# main.net
KiCad netlist of a schematic drawn in Altium Designer
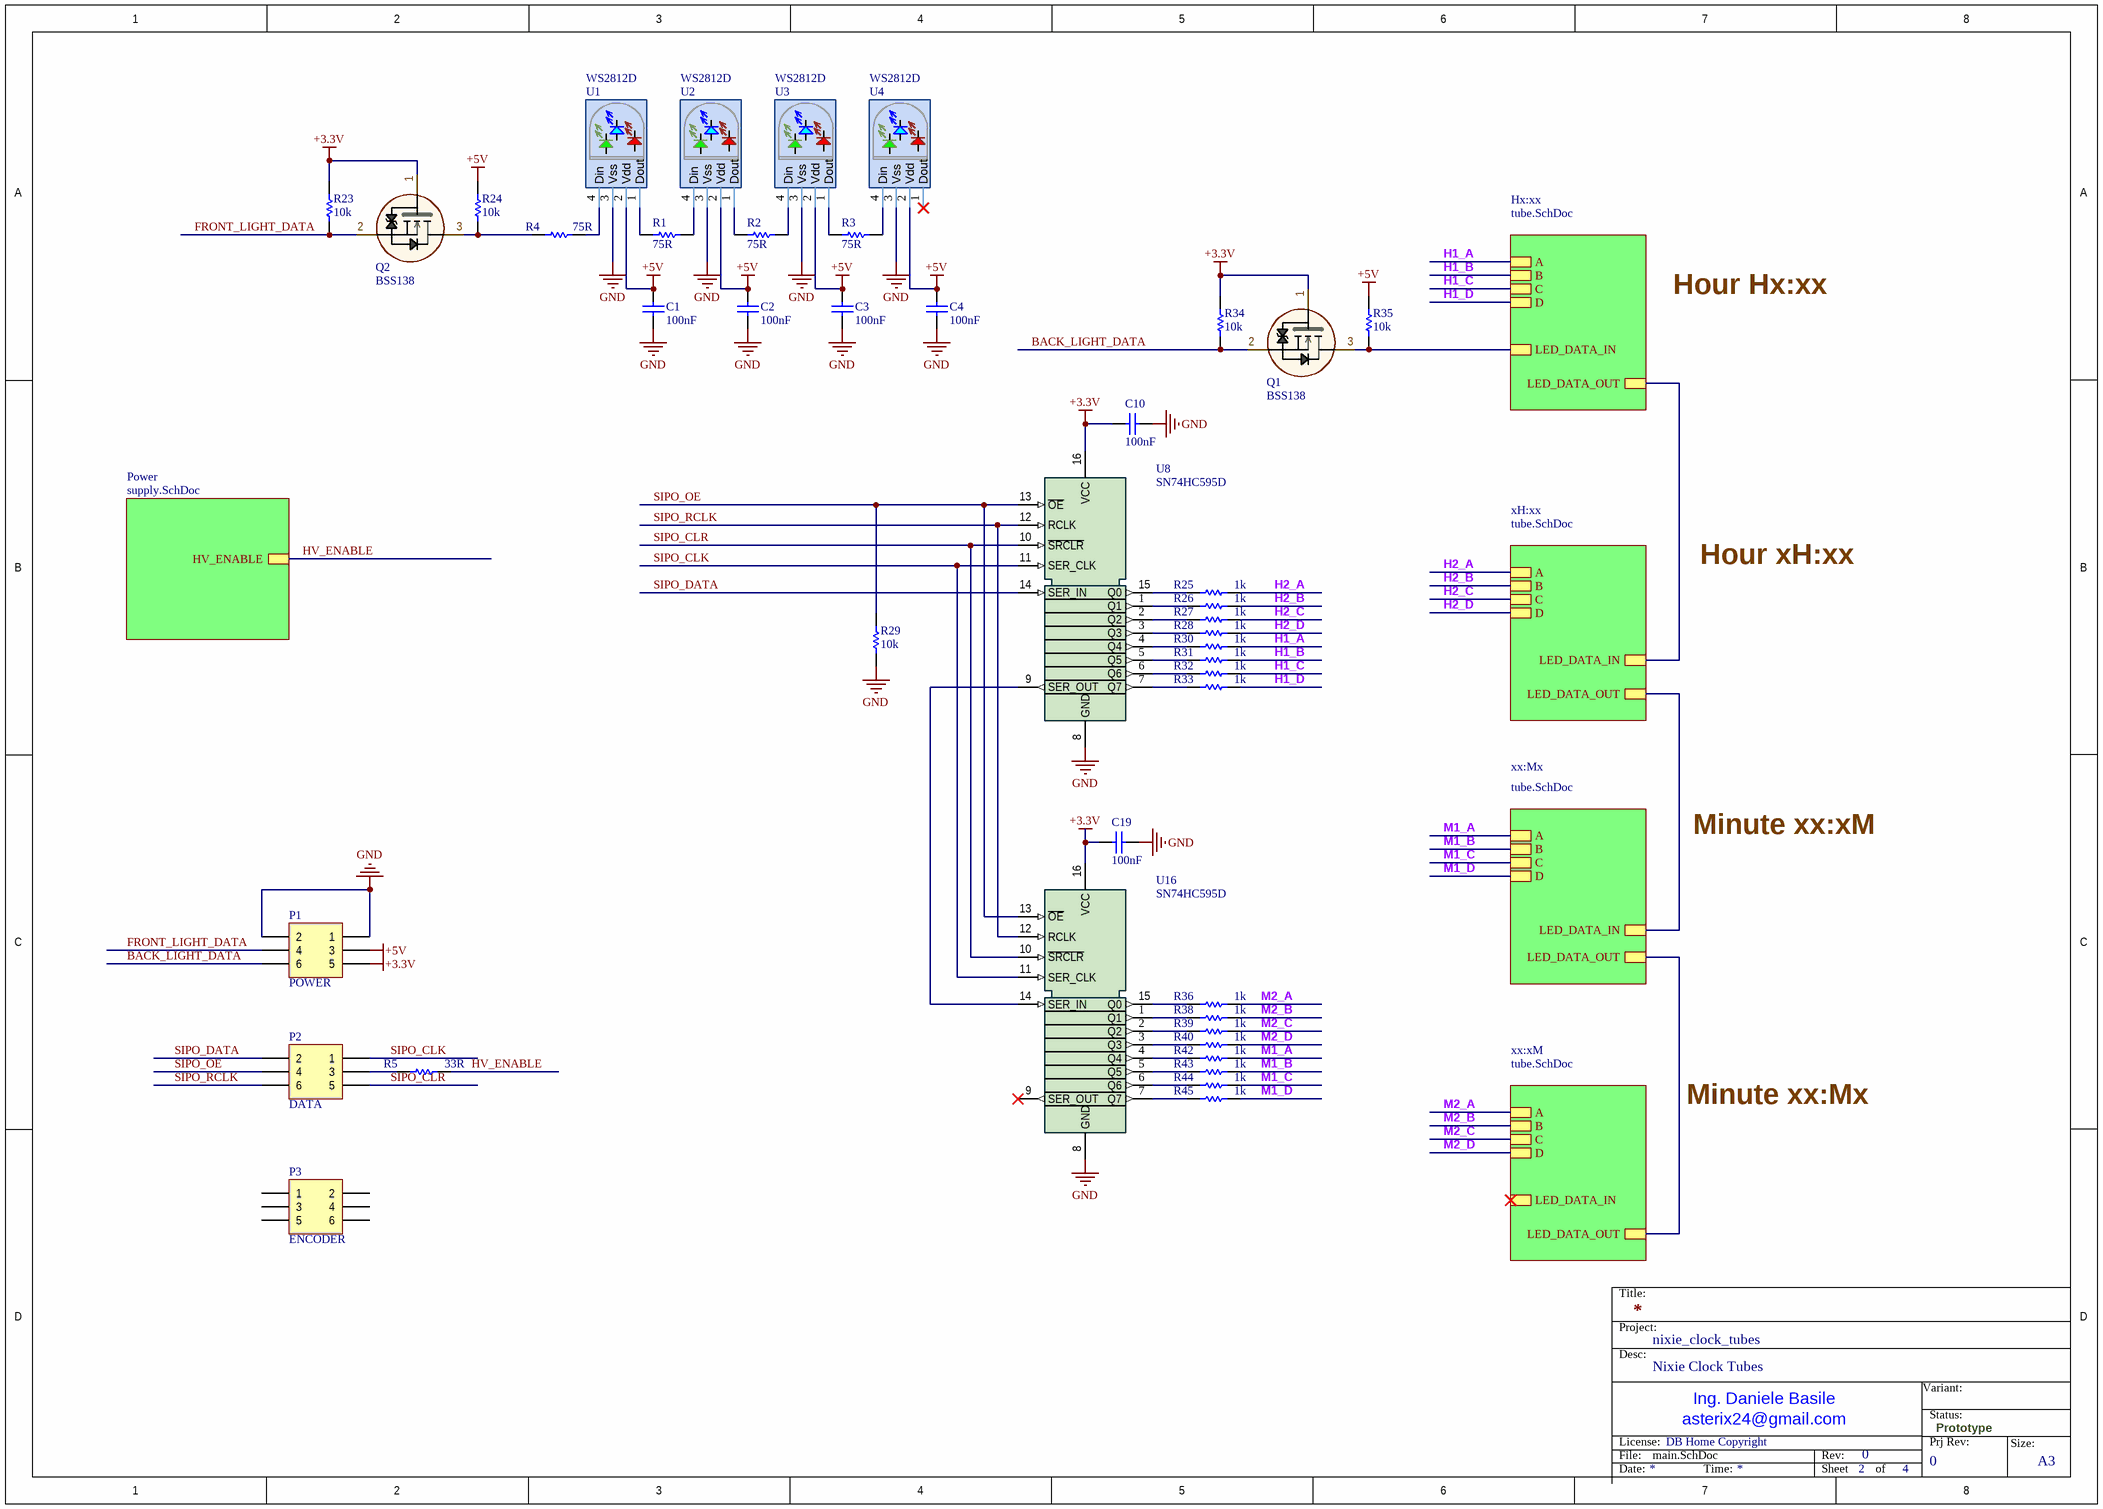
[diagram p0: main.SchDoc]

(export (version "E")
  (design (tool "Eeschema 10.0.6"))
  (components
    (comp (ref "C1")
      (value "100nF")
      (footprint "0603_[1608]")
      (description "Capacitor")
      (libsource (lib "develer_generic") (part "Cap"))
    )
    (comp (ref "C2")
      (value "100nF")
      (footprint "0603_[1608]")
      (description "Capacitor")
      (libsource (lib "develer_generic") (part "Cap"))
    )
    (comp (ref "C3")
      (value "100nF")
      (footprint "0603_[1608]")
      (description "Capacitor")
      (libsource (lib "develer_generic") (part "Cap"))
    )
    (comp (ref "C4")
      (value "100nF")
      (footprint "0603_[1608]")
      (description "Capacitor")
      (libsource (lib "develer_generic") (part "Cap"))
    )
    (comp (ref "C10")
      (value "100nF")
      (footprint "0603_[1608]")
      (description "Capacitor")
      (libsource (lib "develer_generic") (part "Cap"))
    )
    (comp (ref "C19")
      (value "100nF")
      (footprint "0603_[1608]")
      (description "Capacitor")
      (libsource (lib "develer_generic") (part "Cap"))
    )
    (comp (ref "P1")
      (value "POWER")
      (footprint "HEADER_2X3_2.54MM_THD")
      (description "Header, 3-Pin, Dual row")
      (fields (field (name "PUBLISHER") "Altium Limited"))
      (libsource (lib "") (part "Header 3X2_1"))
    )
    (comp (ref "P2")
      (value "DATA")
      (footprint "HEADER_2X3_2.54MM_THD")
      (description "Header, 3-Pin, Dual row")
      (fields (field (name "PUBLISHER") "Altium Limited"))
      (libsource (lib "") (part "Header 3X2_1"))
    )
    (comp (ref "P3")
      (value "ENCODER")
      (footprint "HEADER_2X3_2.54MM_THD")
      (description "Header, 3-Pin, Dual row")
      (fields (field (name "PUBLISHER") "Altium Limited"))
      (libsource (lib "Miscellaneous Connectors") (part "Header 3X2"))
    )
    (comp (ref "Q1")
      (value "BSS138")
      (footprint "SOT-23")
      (description "N-MOSFET 50V 0,22A")
      (fields (field (name "PUBLISHER") "Develer srl"))
      (libsource (lib "develer_components") (part "BSS138"))
    )
    (comp (ref "Q2")
      (value "BSS138")
      (footprint "SOT-23")
      (description "N-MOSFET 50V 0,22A")
      (fields (field (name "PUBLISHER") "Develer srl"))
      (libsource (lib "develer_components") (part "BSS138"))
    )
    (comp (ref "R1")
      (value "75R")
      (footprint "0603_[1608]")
      (description "Resistor")
      (fields (field (name "PUBLISHER") "Develer srl"))
      (libsource (lib "develer_generic") (part "Res"))
    )
    (comp (ref "R2")
      (value "75R")
      (footprint "0603_[1608]")
      (description "Resistor")
      (fields (field (name "PUBLISHER") "Develer srl"))
      (libsource (lib "develer_generic") (part "Res"))
    )
    (comp (ref "R3")
      (value "75R")
      (footprint "0603_[1608]")
      (description "Resistor")
      (fields (field (name "PUBLISHER") "Develer srl"))
      (libsource (lib "develer_generic") (part "Res"))
    )
    (comp (ref "R4")
      (value "75R")
      (footprint "0603_[1608]")
      (description "Resistor")
      (fields (field (name "PUBLISHER") "Develer srl"))
      (libsource (lib "develer_generic") (part "Res"))
    )
    (comp (ref "R5")
      (value "33R")
      (footprint "0603_[1608]")
      (description "Resistor")
      (fields (field (name "PUBLISHER") "Develer srl"))
      (libsource (lib "develer_generic") (part "Res"))
    )
    (comp (ref "R23")
      (value "10k")
      (footprint "0603_[1608]")
      (description "Resistor")
      (fields (field (name "PUBLISHER") "Develer srl"))
      (libsource (lib "develer_generic") (part "Res"))
    )
    (comp (ref "R24")
      (value "10k")
      (footprint "0603_[1608]")
      (description "Resistor")
      (fields (field (name "PUBLISHER") "Develer srl"))
      (libsource (lib "develer_generic") (part "Res"))
    )
    (comp (ref "R25")
      (value "1k")
      (footprint "0603_[1608]")
      (description "Resistor")
      (fields (field (name "PUBLISHER") "Develer srl"))
      (libsource (lib "develer_generic") (part "Res"))
    )
    (comp (ref "R26")
      (value "1k")
      (footprint "0603_[1608]")
      (description "Resistor")
      (fields (field (name "PUBLISHER") "Develer srl"))
      (libsource (lib "develer_generic") (part "Res"))
    )
    (comp (ref "R27")
      (value "1k")
      (footprint "0603_[1608]")
      (description "Resistor")
      (fields (field (name "PUBLISHER") "Develer srl"))
      (libsource (lib "develer_generic") (part "Res"))
    )
    (comp (ref "R28")
      (value "1k")
      (footprint "0603_[1608]")
      (description "Resistor")
      (fields (field (name "PUBLISHER") "Develer srl"))
      (libsource (lib "develer_generic") (part "Res"))
    )
    (comp (ref "R29")
      (value "10k")
      (footprint "0603_[1608]")
      (description "Resistor")
      (fields (field (name "PUBLISHER") "Develer srl"))
      (libsource (lib "develer_generic") (part "Res"))
    )
    (comp (ref "R30")
      (value "1k")
      (footprint "0603_[1608]")
      (description "Resistor")
      (fields (field (name "PUBLISHER") "Develer srl"))
      (libsource (lib "develer_generic") (part "Res"))
    )
    (comp (ref "R31")
      (value "1k")
      (footprint "0603_[1608]")
      (description "Resistor")
      (fields (field (name "PUBLISHER") "Develer srl"))
      (libsource (lib "develer_generic") (part "Res"))
    )
    (comp (ref "R32")
      (value "1k")
      (footprint "0603_[1608]")
      (description "Resistor")
      (fields (field (name "PUBLISHER") "Develer srl"))
      (libsource (lib "develer_generic") (part "Res"))
    )
    (comp (ref "R33")
      (value "1k")
      (footprint "0603_[1608]")
      (description "Resistor")
      (fields (field (name "PUBLISHER") "Develer srl"))
      (libsource (lib "develer_generic") (part "Res"))
    )
    (comp (ref "R34")
      (value "10k")
      (footprint "0603_[1608]")
      (description "Resistor")
      (fields (field (name "PUBLISHER") "Develer srl"))
      (libsource (lib "develer_generic") (part "Res"))
    )
    (comp (ref "R35")
      (value "10k")
      (footprint "0603_[1608]")
      (description "Resistor")
      (fields (field (name "PUBLISHER") "Develer srl"))
      (libsource (lib "develer_generic") (part "Res"))
    )
    (comp (ref "R36")
      (value "1k")
      (footprint "0603_[1608]")
      (description "Resistor")
      (fields (field (name "PUBLISHER") "Develer srl"))
      (libsource (lib "develer_generic") (part "Res"))
    )
    (comp (ref "R38")
      (value "1k")
      (footprint "0603_[1608]")
      (description "Resistor")
      (fields (field (name "PUBLISHER") "Develer srl"))
      (libsource (lib "develer_generic") (part "Res"))
    )
    (comp (ref "R39")
      (value "1k")
      (footprint "0603_[1608]")
      (description "Resistor")
      (fields (field (name "PUBLISHER") "Develer srl"))
      (libsource (lib "develer_generic") (part "Res"))
    )
    (comp (ref "R40")
      (value "1k")
      (footprint "0603_[1608]")
      (description "Resistor")
      (fields (field (name "PUBLISHER") "Develer srl"))
      (libsource (lib "develer_generic") (part "Res"))
    )
    (comp (ref "R42")
      (value "1k")
      (footprint "0603_[1608]")
      (description "Resistor")
      (fields (field (name "PUBLISHER") "Develer srl"))
      (libsource (lib "develer_generic") (part "Res"))
    )
    (comp (ref "R43")
      (value "1k")
      (footprint "0603_[1608]")
      (description "Resistor")
      (fields (field (name "PUBLISHER") "Develer srl"))
      (libsource (lib "develer_generic") (part "Res"))
    )
    (comp (ref "R44")
      (value "1k")
      (footprint "0603_[1608]")
      (description "Resistor")
      (fields (field (name "PUBLISHER") "Develer srl"))
      (libsource (lib "develer_generic") (part "Res"))
    )
    (comp (ref "R45")
      (value "1k")
      (footprint "0603_[1608]")
      (description "Resistor")
      (fields (field (name "PUBLISHER") "Develer srl"))
      (libsource (lib "develer_generic") (part "Res"))
    )
    (comp (ref "U1")
      (value "WS2812D")
      (footprint "R5_RGB_LED_THD")
      (description "Adressable Led RGB 1wire, THD")
      (fields (field (name "PUBLISHER") "Develer srl"))
      (libsource (lib "develer_components") (part "WS2812D"))
    )
    (comp (ref "U2")
      (value "WS2812D")
      (footprint "R5_RGB_LED_THD")
      (description "Adressable Led RGB 1wire, THD")
      (fields (field (name "PUBLISHER") "Develer srl"))
      (libsource (lib "develer_components") (part "WS2812D"))
    )
    (comp (ref "U3")
      (value "WS2812D")
      (footprint "R5_RGB_LED_THD")
      (description "Adressable Led RGB 1wire, THD")
      (fields (field (name "PUBLISHER") "Develer srl"))
      (libsource (lib "develer_components") (part "WS2812D"))
    )
    (comp (ref "U4")
      (value "WS2812D")
      (footprint "R5_RGB_LED_THD")
      (description "Adressable Led RGB 1wire, THD")
      (fields (field (name "PUBLISHER") "Develer srl"))
      (libsource (lib "develer_components") (part "WS2812D"))
    )
    (comp (ref "U8")
      (value "SN74HC595D")
      (footprint "soic16")
      (description "8-Bit Shift Registers With 3-State Output Registers")
      (fields (field (name "PUBLISHER") "Develer srl"))
      (libsource (lib "develer_components") (part "SN74HC595D"))
    )
    (comp (ref "U16")
      (value "SN74HC595D")
      (footprint "soic16")
      (description "8-Bit Shift Registers With 3-State Output Registers")
      (fields (field (name "PUBLISHER") "Develer srl"))
      (libsource (lib "develer_components") (part "SN74HC595D"))
    )
  )
  (nets
    (net (code "1") (name "+3.3V") (class "Default")
      (node (ref "C10") (pin "2") (pinfunction "2_2") (pintype "passive"))
      (node (ref "C19") (pin "2") (pinfunction "2_2") (pintype "passive"))
      (node (ref "P1") (pin "5") (pinfunction "5_5") (pintype "passive"))
      (node (ref "Q1") (pin "1") (pinfunction "G_1") (pintype "passive"))
      (node (ref "Q2") (pin "1") (pinfunction "G_1") (pintype "passive"))
      (node (ref "R23") (pin "1") (pinfunction "1_1") (pintype "passive"))
      (node (ref "R34") (pin "1") (pinfunction "1_1") (pintype "passive"))
      (node (ref "U16") (pin "16") (pinfunction "VCC_16") (pintype "power_in"))
      (node (ref "U8") (pin "16") (pinfunction "VCC_16") (pintype "power_in"))
    )
    (net (code "2") (name "+5V") (class "Default")
      (node (ref "C1") (pin "1") (pinfunction "1_1") (pintype "passive"))
      (node (ref "C2") (pin "1") (pinfunction "1_1") (pintype "passive"))
      (node (ref "C3") (pin "1") (pinfunction "1_1") (pintype "passive"))
      (node (ref "C4") (pin "1") (pinfunction "1_1") (pintype "passive"))
      (node (ref "P1") (pin "3") (pinfunction "3_3") (pintype "passive"))
      (node (ref "R24") (pin "1") (pinfunction "1_1") (pintype "passive"))
      (node (ref "R35") (pin "1") (pinfunction "1_1") (pintype "passive"))
      (node (ref "U1") (pin "2") (pinfunction "Vdd_2") (pintype "passive"))
      (node (ref "U2") (pin "2") (pinfunction "Vdd_2") (pintype "passive"))
      (node (ref "U3") (pin "2") (pinfunction "Vdd_2") (pintype "passive"))
      (node (ref "U4") (pin "2") (pinfunction "Vdd_2") (pintype "passive"))
    )
    (net (code "3") (name "/BACK_LIGHT_DATA") (class "Default")
      (node (ref "P1") (pin "6") (pinfunction "6_6") (pintype "passive"))
      (node (ref "Q1") (pin "2") (pinfunction "S_2") (pintype "passive"))
      (node (ref "R34") (pin "2") (pinfunction "2_2") (pintype "passive"))
    )
    (net (code "4") (name "/FRONT_LIGHT_DATA") (class "Default")
      (node (ref "P1") (pin "4") (pinfunction "4_4") (pintype "passive"))
      (node (ref "Q2") (pin "2") (pinfunction "S_2") (pintype "passive"))
      (node (ref "R23") (pin "2") (pinfunction "2_2") (pintype "passive"))
    )
    (net (code "5") (name "/H1_A") (class "Default")
      (node (ref "R30") (pin "1") (pinfunction "1_1") (pintype "passive"))
    )
    (net (code "6") (name "/H1_B") (class "Default")
      (node (ref "R31") (pin "1") (pinfunction "1_1") (pintype "passive"))
    )
    (net (code "7") (name "/H1_C") (class "Default")
      (node (ref "R32") (pin "1") (pinfunction "1_1") (pintype "passive"))
    )
    (net (code "8") (name "/H1_D") (class "Default")
      (node (ref "R33") (pin "1") (pinfunction "1_1") (pintype "passive"))
    )
    (net (code "9") (name "/H2_A") (class "Default")
      (node (ref "R25") (pin "1") (pinfunction "1_1") (pintype "passive"))
    )
    (net (code "10") (name "/H2_B") (class "Default")
      (node (ref "R26") (pin "1") (pinfunction "1_1") (pintype "passive"))
    )
    (net (code "11") (name "/H2_C") (class "Default")
      (node (ref "R27") (pin "1") (pinfunction "1_1") (pintype "passive"))
    )
    (net (code "12") (name "/H2_D") (class "Default")
      (node (ref "R28") (pin "1") (pinfunction "1_1") (pintype "passive"))
    )
    (net (code "13") (name "/HV_ENABLE") (class "Default")
      (node (ref "R5") (pin "1") (pinfunction "1_1") (pintype "passive"))
    )
    (net (code "14") (name "/LED_DATA_IN") (class "Default")
      (node (ref "Q1") (pin "3") (pinfunction "D_3") (pintype "passive"))
      (node (ref "R35") (pin "2") (pinfunction "2_2") (pintype "passive"))
    )
    (net (code "19") (name "/M1_A") (class "Default")
      (node (ref "R42") (pin "1") (pinfunction "1_1") (pintype "passive"))
    )
    (net (code "20") (name "/M1_B") (class "Default")
      (node (ref "R43") (pin "1") (pinfunction "1_1") (pintype "passive"))
    )
    (net (code "21") (name "/M1_C") (class "Default")
      (node (ref "R44") (pin "1") (pinfunction "1_1") (pintype "passive"))
    )
    (net (code "22") (name "/M1_D") (class "Default")
      (node (ref "R45") (pin "1") (pinfunction "1_1") (pintype "passive"))
    )
    (net (code "23") (name "/M2_A") (class "Default")
      (node (ref "R36") (pin "1") (pinfunction "1_1") (pintype "passive"))
    )
    (net (code "24") (name "/M2_B") (class "Default")
      (node (ref "R38") (pin "1") (pinfunction "1_1") (pintype "passive"))
    )
    (net (code "25") (name "/M2_C") (class "Default")
      (node (ref "R39") (pin "1") (pinfunction "1_1") (pintype "passive"))
    )
    (net (code "26") (name "/M2_D") (class "Default")
      (node (ref "R40") (pin "1") (pinfunction "1_1") (pintype "passive"))
    )
    (net (code "27") (name "/SIPO_CLK") (class "Default")
      (node (ref "P2") (pin "1") (pinfunction "1_1") (pintype "passive"))
      (node (ref "U16") (pin "11") (pinfunction "SER_CLK_11") (pintype "input"))
      (node (ref "U8") (pin "11") (pinfunction "SER_CLK_11") (pintype "input"))
    )
    (net (code "28") (name "/SIPO_CLR") (class "Default")
      (node (ref "P2") (pin "5") (pinfunction "5_5") (pintype "passive"))
      (node (ref "U16") (pin "10") (pinfunction "~{SRCLR}_10") (pintype "input"))
      (node (ref "U8") (pin "10") (pinfunction "~{SRCLR}_10") (pintype "input"))
    )
    (net (code "29") (name "/SIPO_DATA") (class "Default")
      (node (ref "P2") (pin "2") (pinfunction "2_2") (pintype "passive"))
      (node (ref "U8") (pin "14") (pinfunction "SER_IN_14") (pintype "input"))
    )
    (net (code "30") (name "/SIPO_OE") (class "Default")
      (node (ref "P2") (pin "4") (pinfunction "4_4") (pintype "passive"))
      (node (ref "R29") (pin "1") (pinfunction "1_1") (pintype "passive"))
      (node (ref "U16") (pin "13") (pinfunction "~{OE}_13") (pintype "input"))
      (node (ref "U8") (pin "13") (pinfunction "~{OE}_13") (pintype "input"))
    )
    (net (code "31") (name "/SIPO_RCLK") (class "Default")
      (node (ref "P2") (pin "6") (pinfunction "6_6") (pintype "passive"))
      (node (ref "U16") (pin "12") (pinfunction "RCLK_12") (pintype "input"))
      (node (ref "U8") (pin "12") (pinfunction "RCLK_12") (pintype "input"))
    )
    (net (code "32") (name "GND") (class "Default")
      (node (ref "C1") (pin "2") (pinfunction "2_2") (pintype "passive"))
      (node (ref "C10") (pin "1") (pinfunction "1_1") (pintype "passive"))
      (node (ref "C19") (pin "1") (pinfunction "1_1") (pintype "passive"))
      (node (ref "C2") (pin "2") (pinfunction "2_2") (pintype "passive"))
      (node (ref "C3") (pin "2") (pinfunction "2_2") (pintype "passive"))
      (node (ref "C4") (pin "2") (pinfunction "2_2") (pintype "passive"))
      (node (ref "P1") (pin "1") (pinfunction "1_1") (pintype "passive"))
      (node (ref "P1") (pin "2") (pinfunction "2_2") (pintype "passive"))
      (node (ref "R29") (pin "2") (pinfunction "2_2") (pintype "passive"))
      (node (ref "U1") (pin "3") (pinfunction "Vss_3") (pintype "passive"))
      (node (ref "U16") (pin "8") (pinfunction "GND_8") (pintype "power_in"))
      (node (ref "U2") (pin "3") (pinfunction "Vss_3") (pintype "passive"))
      (node (ref "U3") (pin "3") (pinfunction "Vss_3") (pintype "passive"))
      (node (ref "U4") (pin "3") (pinfunction "Vss_3") (pintype "passive"))
      (node (ref "U8") (pin "8") (pinfunction "GND_8") (pintype "power_in"))
    )
    (net (code "33") (name "Net-(P2-Pad3)") (class "Default")
      (node (ref "P2") (pin "3") (pinfunction "3_3") (pintype "passive"))
      (node (ref "R5") (pin "2") (pinfunction "2_2") (pintype "passive"))
    )
    (net (code "34") (name "Net-(Q2-D)") (class "Default")
      (node (ref "Q2") (pin "3") (pinfunction "D_3") (pintype "passive"))
      (node (ref "R24") (pin "2") (pinfunction "2_2") (pintype "passive"))
      (node (ref "R4") (pin "2") (pinfunction "2_2") (pintype "passive"))
    )
    (net (code "35") (name "Net-(U1-Din)") (class "Default")
      (node (ref "R4") (pin "1") (pinfunction "1_1") (pintype "passive"))
      (node (ref "U1") (pin "4") (pinfunction "Din_4") (pintype "passive"))
    )
    (net (code "36") (name "Net-(U1-Dout)") (class "Default")
      (node (ref "R1") (pin "1") (pinfunction "1_1") (pintype "passive"))
      (node (ref "U1") (pin "1") (pinfunction "Dout_1") (pintype "passive"))
    )
    (net (code "37") (name "Net-(U2-Din)") (class "Default")
      (node (ref "R1") (pin "2") (pinfunction "2_2") (pintype "passive"))
      (node (ref "U2") (pin "4") (pinfunction "Din_4") (pintype "passive"))
    )
    (net (code "38") (name "Net-(U2-Dout)") (class "Default")
      (node (ref "R2") (pin "1") (pinfunction "1_1") (pintype "passive"))
      (node (ref "U2") (pin "1") (pinfunction "Dout_1") (pintype "passive"))
    )
    (net (code "39") (name "Net-(U3-Din)") (class "Default")
      (node (ref "R2") (pin "2") (pinfunction "2_2") (pintype "passive"))
      (node (ref "U3") (pin "4") (pinfunction "Din_4") (pintype "passive"))
    )
    (net (code "40") (name "Net-(U3-Dout)") (class "Default")
      (node (ref "R3") (pin "1") (pinfunction "1_1") (pintype "passive"))
      (node (ref "U3") (pin "1") (pinfunction "Dout_1") (pintype "passive"))
    )
    (net (code "41") (name "Net-(U4-Din)") (class "Default")
      (node (ref "R3") (pin "2") (pinfunction "2_2") (pintype "passive"))
      (node (ref "U4") (pin "4") (pinfunction "Din_4") (pintype "passive"))
    )
    (net (code "42") (name "Net-(U8-Q0)") (class "Default")
      (node (ref "R25") (pin "2") (pinfunction "2_2") (pintype "passive"))
      (node (ref "U8") (pin "15") (pinfunction "Q0_15") (pintype "output"))
    )
    (net (code "43") (name "Net-(U8-Q1)") (class "Default")
      (node (ref "R26") (pin "2") (pinfunction "2_2") (pintype "passive"))
      (node (ref "U8") (pin "1") (pinfunction "Q1_1") (pintype "output"))
    )
    (net (code "44") (name "Net-(U8-Q2)") (class "Default")
      (node (ref "R27") (pin "2") (pinfunction "2_2") (pintype "passive"))
      (node (ref "U8") (pin "2") (pinfunction "Q2_2") (pintype "output"))
    )
    (net (code "45") (name "Net-(U8-Q3)") (class "Default")
      (node (ref "R28") (pin "2") (pinfunction "2_2") (pintype "passive"))
      (node (ref "U8") (pin "3") (pinfunction "Q3_3") (pintype "output"))
    )
    (net (code "46") (name "Net-(U8-Q4)") (class "Default")
      (node (ref "R30") (pin "2") (pinfunction "2_2") (pintype "passive"))
      (node (ref "U8") (pin "4") (pinfunction "Q4_4") (pintype "output"))
    )
    (net (code "47") (name "Net-(U8-Q5)") (class "Default")
      (node (ref "R31") (pin "2") (pinfunction "2_2") (pintype "passive"))
      (node (ref "U8") (pin "5") (pinfunction "Q5_5") (pintype "output"))
    )
    (net (code "48") (name "Net-(U8-Q6)") (class "Default")
      (node (ref "R32") (pin "2") (pinfunction "2_2") (pintype "passive"))
      (node (ref "U8") (pin "6") (pinfunction "Q6_6") (pintype "output"))
    )
    (net (code "49") (name "Net-(U8-Q7)") (class "Default")
      (node (ref "R33") (pin "2") (pinfunction "2_2") (pintype "passive"))
      (node (ref "U8") (pin "7") (pinfunction "Q7_7") (pintype "output"))
    )
    (net (code "50") (name "Net-(U16-Q0)") (class "Default")
      (node (ref "R36") (pin "2") (pinfunction "2_2") (pintype "passive"))
      (node (ref "U16") (pin "15") (pinfunction "Q0_15") (pintype "output"))
    )
    (net (code "51") (name "Net-(U16-Q1)") (class "Default")
      (node (ref "R38") (pin "2") (pinfunction "2_2") (pintype "passive"))
      (node (ref "U16") (pin "1") (pinfunction "Q1_1") (pintype "output"))
    )
    (net (code "52") (name "Net-(U16-Q2)") (class "Default")
      (node (ref "R39") (pin "2") (pinfunction "2_2") (pintype "passive"))
      (node (ref "U16") (pin "2") (pinfunction "Q2_2") (pintype "output"))
    )
    (net (code "53") (name "Net-(U16-Q3)") (class "Default")
      (node (ref "R40") (pin "2") (pinfunction "2_2") (pintype "passive"))
      (node (ref "U16") (pin "3") (pinfunction "Q3_3") (pintype "output"))
    )
    (net (code "54") (name "Net-(U16-Q4)") (class "Default")
      (node (ref "R42") (pin "2") (pinfunction "2_2") (pintype "passive"))
      (node (ref "U16") (pin "4") (pinfunction "Q4_4") (pintype "output"))
    )
    (net (code "55") (name "Net-(U16-Q5)") (class "Default")
      (node (ref "R43") (pin "2") (pinfunction "2_2") (pintype "passive"))
      (node (ref "U16") (pin "5") (pinfunction "Q5_5") (pintype "output"))
    )
    (net (code "56") (name "Net-(U16-Q6)") (class "Default")
      (node (ref "R44") (pin "2") (pinfunction "2_2") (pintype "passive"))
      (node (ref "U16") (pin "6") (pinfunction "Q6_6") (pintype "output"))
    )
    (net (code "57") (name "Net-(U16-Q7)") (class "Default")
      (node (ref "R45") (pin "2") (pinfunction "2_2") (pintype "passive"))
      (node (ref "U16") (pin "7") (pinfunction "Q7_7") (pintype "output"))
    )
    (net (code "58") (name "Net-(U16-SER_IN)") (class "Default")
      (node (ref "U16") (pin "14") (pinfunction "SER_IN_14") (pintype "input"))
      (node (ref "U8") (pin "9") (pinfunction "SER_OUT_9") (pintype "output"))
    )
    (net (code "59") (name "unconnected-(P3-Pad1)") (class "Default")
      (node (ref "P3") (pin "1") (pinfunction "1_1") (pintype "passive"))
    )
    (net (code "60") (name "unconnected-(P3-Pad2)") (class "Default")
      (node (ref "P3") (pin "2") (pinfunction "2_2") (pintype "passive"))
    )
    (net (code "61") (name "unconnected-(P3-Pad3)") (class "Default")
      (node (ref "P3") (pin "3") (pinfunction "3_3") (pintype "passive"))
    )
    (net (code "62") (name "unconnected-(P3-Pad4)") (class "Default")
      (node (ref "P3") (pin "4") (pinfunction "4_4") (pintype "passive"))
    )
    (net (code "63") (name "unconnected-(P3-Pad5)") (class "Default")
      (node (ref "P3") (pin "5") (pinfunction "5_5") (pintype "passive"))
    )
    (net (code "64") (name "unconnected-(P3-Pad6)") (class "Default")
      (node (ref "P3") (pin "6") (pinfunction "6_6") (pintype "passive"))
    )
    (net (code "65") (name "unconnected-(U4-Dout-Pad1)") (class "Default")
      (node (ref "U4") (pin "1") (pinfunction "Dout_1") (pintype "passive+no_connect"))
    )
    (net (code "66") (name "unconnected-(U16-SER_OUT-Pad9)") (class "Default")
      (node (ref "U16") (pin "9") (pinfunction "SER_OUT_9") (pintype "output+no_connect"))
    )
  )
)
